# DUCO_Miner_16-01.net
KiCad netlist of a schematic drawn in EAGLE
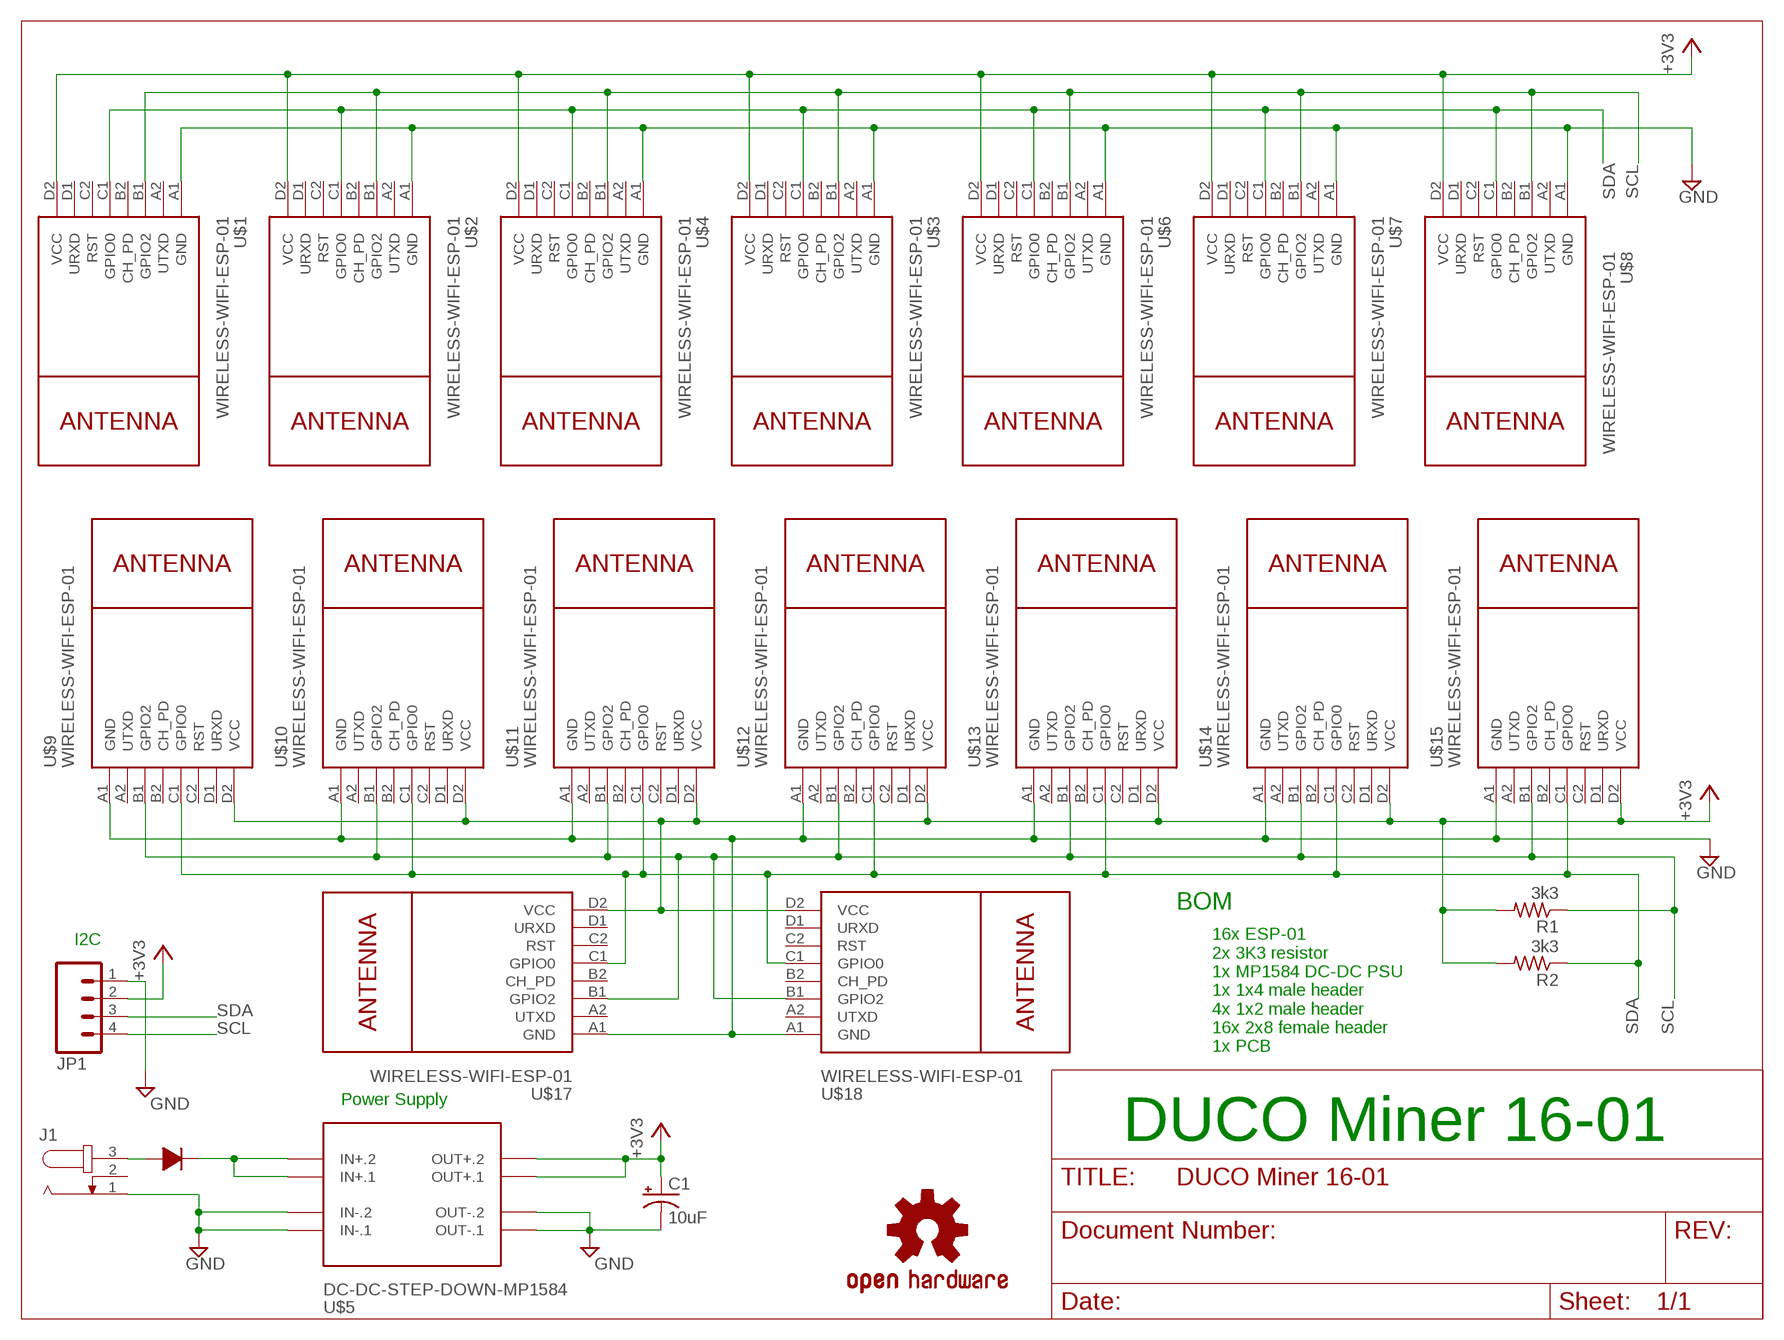
[diagram p0: schematic, sheet 1]

(export (version "E")
  (design (tool "Eeschema 10.0.6"))
  (components
    (comp (ref "C1")
      (value "10uF")
      (footprint "eagle-import:E2-5")
      (libsource (lib "eagle-import") (part "CPOL-USE2-5"))
    )
    (comp (ref "J1")
      (value "JACK-PLUG0")
      (footprint "eagle-import:SPC4077")
      (libsource (lib "eagle-import") (part "JACK-PLUG0"))
    )
    (comp (ref "JP1")
      (value "M04PTH")
      (footprint "eagle-import:1X04")
      (libsource (lib "eagle-import") (part "M04PTH"))
    )
    (comp (ref "LOGO1")
      (value "OSHW-LOGOL")
      (footprint "eagle-import:OSHW-LOGO-L")
      (libsource (lib "eagle-import") (part "OSHW-LOGOL"))
    )
    (comp (ref "R1")
      (value "3k3")
      (footprint "eagle-import:0204_7")
      (libsource (lib "eagle-import") (part "R-US_0204/7"))
    )
    (comp (ref "R2")
      (value "3k3")
      (footprint "eagle-import:0204_7")
      (libsource (lib "eagle-import") (part "R-US_0204/7"))
    )
    (comp (ref "U$1")
      (value "WIRELESS-WIFI-ESP-01")
      (footprint "eagle-import:WIRELESS-WIFI-ESP-01")
      (libsource (lib "eagle-import") (part "WIRELESS-WIFI-ESP-01"))
    )
    (comp (ref "U$2")
      (value "WIRELESS-WIFI-ESP-01")
      (footprint "eagle-import:WIRELESS-WIFI-ESP-01")
      (libsource (lib "eagle-import") (part "WIRELESS-WIFI-ESP-01"))
    )
    (comp (ref "U$3")
      (value "WIRELESS-WIFI-ESP-01")
      (footprint "eagle-import:WIRELESS-WIFI-ESP-01")
      (libsource (lib "eagle-import") (part "WIRELESS-WIFI-ESP-01"))
    )
    (comp (ref "U$4")
      (value "WIRELESS-WIFI-ESP-01")
      (footprint "eagle-import:WIRELESS-WIFI-ESP-01")
      (libsource (lib "eagle-import") (part "WIRELESS-WIFI-ESP-01"))
    )
    (comp (ref "U$5")
      (value "DC-DC-STEP-DOWN-MP1584")
      (footprint "eagle-import:DC-DC-STEP-DOWN-MP1584")
      (libsource (lib "eagle-import") (part "DC-DC-STEP-DOWN-MP1584"))
    )
    (comp (ref "U$6")
      (value "WIRELESS-WIFI-ESP-01")
      (footprint "eagle-import:WIRELESS-WIFI-ESP-01")
      (libsource (lib "eagle-import") (part "WIRELESS-WIFI-ESP-01"))
    )
    (comp (ref "U$7")
      (value "WIRELESS-WIFI-ESP-01")
      (footprint "eagle-import:WIRELESS-WIFI-ESP-01")
      (libsource (lib "eagle-import") (part "WIRELESS-WIFI-ESP-01"))
    )
    (comp (ref "U$8")
      (value "WIRELESS-WIFI-ESP-01")
      (footprint "eagle-import:WIRELESS-WIFI-ESP-01")
      (libsource (lib "eagle-import") (part "WIRELESS-WIFI-ESP-01"))
    )
    (comp (ref "U$9")
      (value "WIRELESS-WIFI-ESP-01")
      (footprint "eagle-import:WIRELESS-WIFI-ESP-01")
      (libsource (lib "eagle-import") (part "WIRELESS-WIFI-ESP-01"))
    )
    (comp (ref "U$10")
      (value "WIRELESS-WIFI-ESP-01")
      (footprint "eagle-import:WIRELESS-WIFI-ESP-01")
      (libsource (lib "eagle-import") (part "WIRELESS-WIFI-ESP-01"))
    )
    (comp (ref "U$11")
      (value "WIRELESS-WIFI-ESP-01")
      (footprint "eagle-import:WIRELESS-WIFI-ESP-01")
      (libsource (lib "eagle-import") (part "WIRELESS-WIFI-ESP-01"))
    )
    (comp (ref "U$12")
      (value "WIRELESS-WIFI-ESP-01")
      (footprint "eagle-import:WIRELESS-WIFI-ESP-01")
      (libsource (lib "eagle-import") (part "WIRELESS-WIFI-ESP-01"))
    )
    (comp (ref "U$13")
      (value "WIRELESS-WIFI-ESP-01")
      (footprint "eagle-import:WIRELESS-WIFI-ESP-01")
      (libsource (lib "eagle-import") (part "WIRELESS-WIFI-ESP-01"))
    )
    (comp (ref "U$14")
      (value "WIRELESS-WIFI-ESP-01")
      (footprint "eagle-import:WIRELESS-WIFI-ESP-01")
      (libsource (lib "eagle-import") (part "WIRELESS-WIFI-ESP-01"))
    )
    (comp (ref "U$15")
      (value "WIRELESS-WIFI-ESP-01")
      (footprint "eagle-import:WIRELESS-WIFI-ESP-01")
      (libsource (lib "eagle-import") (part "WIRELESS-WIFI-ESP-01"))
    )
    (comp (ref "U$16")
      (value "1N4001")
      (footprint "eagle-import:DIODE-12.70")
      (libsource (lib "eagle-import") (part "1N4001"))
    )
    (comp (ref "U$17")
      (value "WIRELESS-WIFI-ESP-01")
      (footprint "eagle-import:WIRELESS-WIFI-ESP-01")
      (libsource (lib "eagle-import") (part "WIRELESS-WIFI-ESP-01"))
    )
    (comp (ref "U$18")
      (value "WIRELESS-WIFI-ESP-01")
      (footprint "eagle-import:WIRELESS-WIFI-ESP-01")
      (libsource (lib "eagle-import") (part "WIRELESS-WIFI-ESP-01"))
    )
  )
  (nets
    (net (code "1") (name "+3V3") (class "Default")
      (node (ref "C1") (pin "+") (pinfunction "+_+") (pintype "passive"))
      (node (ref "JP1") (pin "2") (pinfunction "2_2") (pintype "passive"))
      (node (ref "R1") (pin "2") (pinfunction "2_2") (pintype "passive"))
      (node (ref "R2") (pin "2") (pinfunction "2_2") (pintype "passive"))
      (node (ref "U$1") (pin "D2") (pinfunction "VCC_D2") (pintype "power_in"))
      (node (ref "U$10") (pin "D2") (pinfunction "VCC_D2") (pintype "power_in"))
      (node (ref "U$11") (pin "D2") (pinfunction "VCC_D2") (pintype "power_in"))
      (node (ref "U$12") (pin "D2") (pinfunction "VCC_D2") (pintype "power_in"))
      (node (ref "U$13") (pin "D2") (pinfunction "VCC_D2") (pintype "power_in"))
      (node (ref "U$14") (pin "D2") (pinfunction "VCC_D2") (pintype "power_in"))
      (node (ref "U$15") (pin "D2") (pinfunction "VCC_D2") (pintype "power_in"))
      (node (ref "U$17") (pin "D2") (pinfunction "VCC_D2") (pintype "power_in"))
      (node (ref "U$18") (pin "D2") (pinfunction "VCC_D2") (pintype "power_in"))
      (node (ref "U$2") (pin "D2") (pinfunction "VCC_D2") (pintype "power_in"))
      (node (ref "U$3") (pin "D2") (pinfunction "VCC_D2") (pintype "power_in"))
      (node (ref "U$4") (pin "D2") (pinfunction "VCC_D2") (pintype "power_in"))
      (node (ref "U$5") (pin "OUT+.1") (pinfunction "OUT+.1_OUT+.1") (pintype "bidirectional"))
      (node (ref "U$5") (pin "OUT+.2") (pinfunction "OUT+.2_OUT+.2") (pintype "bidirectional"))
      (node (ref "U$6") (pin "D2") (pinfunction "VCC_D2") (pintype "power_in"))
      (node (ref "U$7") (pin "D2") (pinfunction "VCC_D2") (pintype "power_in"))
      (node (ref "U$8") (pin "D2") (pinfunction "VCC_D2") (pintype "power_in"))
      (node (ref "U$9") (pin "D2") (pinfunction "VCC_D2") (pintype "power_in"))
    )
    (net (code "2") (name "/SCL") (class "Default")
      (node (ref "JP1") (pin "4") (pinfunction "4_4") (pintype "passive"))
      (node (ref "R1") (pin "1") (pinfunction "1_1") (pintype "passive"))
      (node (ref "U$1") (pin "B1") (pinfunction "GPIO2_B1") (pintype "bidirectional"))
      (node (ref "U$10") (pin "B1") (pinfunction "GPIO2_B1") (pintype "bidirectional"))
      (node (ref "U$11") (pin "B1") (pinfunction "GPIO2_B1") (pintype "bidirectional"))
      (node (ref "U$12") (pin "B1") (pinfunction "GPIO2_B1") (pintype "bidirectional"))
      (node (ref "U$13") (pin "B1") (pinfunction "GPIO2_B1") (pintype "bidirectional"))
      (node (ref "U$14") (pin "B1") (pinfunction "GPIO2_B1") (pintype "bidirectional"))
      (node (ref "U$15") (pin "B1") (pinfunction "GPIO2_B1") (pintype "bidirectional"))
      (node (ref "U$17") (pin "B1") (pinfunction "GPIO2_B1") (pintype "bidirectional"))
      (node (ref "U$18") (pin "B1") (pinfunction "GPIO2_B1") (pintype "bidirectional"))
      (node (ref "U$2") (pin "B1") (pinfunction "GPIO2_B1") (pintype "bidirectional"))
      (node (ref "U$3") (pin "B1") (pinfunction "GPIO2_B1") (pintype "bidirectional"))
      (node (ref "U$4") (pin "B1") (pinfunction "GPIO2_B1") (pintype "bidirectional"))
      (node (ref "U$6") (pin "B1") (pinfunction "GPIO2_B1") (pintype "bidirectional"))
      (node (ref "U$7") (pin "B1") (pinfunction "GPIO2_B1") (pintype "bidirectional"))
      (node (ref "U$8") (pin "B1") (pinfunction "GPIO2_B1") (pintype "bidirectional"))
      (node (ref "U$9") (pin "B1") (pinfunction "GPIO2_B1") (pintype "bidirectional"))
    )
    (net (code "3") (name "/SDA") (class "Default")
      (node (ref "JP1") (pin "3") (pinfunction "3_3") (pintype "passive"))
      (node (ref "R2") (pin "1") (pinfunction "1_1") (pintype "passive"))
      (node (ref "U$1") (pin "C1") (pinfunction "GPIO0_C1") (pintype "bidirectional"))
      (node (ref "U$10") (pin "C1") (pinfunction "GPIO0_C1") (pintype "bidirectional"))
      (node (ref "U$11") (pin "C1") (pinfunction "GPIO0_C1") (pintype "bidirectional"))
      (node (ref "U$12") (pin "C1") (pinfunction "GPIO0_C1") (pintype "bidirectional"))
      (node (ref "U$13") (pin "C1") (pinfunction "GPIO0_C1") (pintype "bidirectional"))
      (node (ref "U$14") (pin "C1") (pinfunction "GPIO0_C1") (pintype "bidirectional"))
      (node (ref "U$15") (pin "C1") (pinfunction "GPIO0_C1") (pintype "bidirectional"))
      (node (ref "U$17") (pin "C1") (pinfunction "GPIO0_C1") (pintype "bidirectional"))
      (node (ref "U$18") (pin "C1") (pinfunction "GPIO0_C1") (pintype "bidirectional"))
      (node (ref "U$2") (pin "C1") (pinfunction "GPIO0_C1") (pintype "bidirectional"))
      (node (ref "U$3") (pin "C1") (pinfunction "GPIO0_C1") (pintype "bidirectional"))
      (node (ref "U$4") (pin "C1") (pinfunction "GPIO0_C1") (pintype "bidirectional"))
      (node (ref "U$6") (pin "C1") (pinfunction "GPIO0_C1") (pintype "bidirectional"))
      (node (ref "U$7") (pin "C1") (pinfunction "GPIO0_C1") (pintype "bidirectional"))
      (node (ref "U$8") (pin "C1") (pinfunction "GPIO0_C1") (pintype "bidirectional"))
      (node (ref "U$9") (pin "C1") (pinfunction "GPIO0_C1") (pintype "bidirectional"))
    )
    (net (code "4") (name "GND") (class "Default")
      (node (ref "C1") (pin "-") (pinfunction "-_-") (pintype "passive"))
      (node (ref "J1") (pin "1") (pinfunction "1_1") (pintype "passive"))
      (node (ref "JP1") (pin "1") (pinfunction "1_1") (pintype "passive"))
      (node (ref "U$1") (pin "A1") (pinfunction "GND_A1") (pintype "power_in"))
      (node (ref "U$10") (pin "A1") (pinfunction "GND_A1") (pintype "power_in"))
      (node (ref "U$11") (pin "A1") (pinfunction "GND_A1") (pintype "power_in"))
      (node (ref "U$12") (pin "A1") (pinfunction "GND_A1") (pintype "power_in"))
      (node (ref "U$13") (pin "A1") (pinfunction "GND_A1") (pintype "power_in"))
      (node (ref "U$14") (pin "A1") (pinfunction "GND_A1") (pintype "power_in"))
      (node (ref "U$15") (pin "A1") (pinfunction "GND_A1") (pintype "power_in"))
      (node (ref "U$17") (pin "A1") (pinfunction "GND_A1") (pintype "power_in"))
      (node (ref "U$18") (pin "A1") (pinfunction "GND_A1") (pintype "power_in"))
      (node (ref "U$2") (pin "A1") (pinfunction "GND_A1") (pintype "power_in"))
      (node (ref "U$3") (pin "A1") (pinfunction "GND_A1") (pintype "power_in"))
      (node (ref "U$4") (pin "A1") (pinfunction "GND_A1") (pintype "power_in"))
      (node (ref "U$5") (pin "IN-.1") (pinfunction "IN-.1_IN-.1") (pintype "bidirectional"))
      (node (ref "U$5") (pin "IN-.2") (pinfunction "IN-.2_IN-.2") (pintype "bidirectional"))
      (node (ref "U$5") (pin "OUT-.1") (pinfunction "OUT-.1_OUT-.1") (pintype "bidirectional"))
      (node (ref "U$5") (pin "OUT-.2") (pinfunction "OUT-.2_OUT-.2") (pintype "bidirectional"))
      (node (ref "U$6") (pin "A1") (pinfunction "GND_A1") (pintype "power_in"))
      (node (ref "U$7") (pin "A1") (pinfunction "GND_A1") (pintype "power_in"))
      (node (ref "U$8") (pin "A1") (pinfunction "GND_A1") (pintype "power_in"))
      (node (ref "U$9") (pin "A1") (pinfunction "GND_A1") (pintype "power_in"))
    )
    (net (code "5") (name "Net-(J1-Pad3)") (class "Default")
      (node (ref "J1") (pin "3") (pinfunction "3_3") (pintype "passive"))
      (node (ref "U$16") (pin "P$1") (pinfunction "P$1_P$1") (pintype "passive"))
    )
    (net (code "6") (name "Net-(U$16-PadP$2)") (class "Default")
      (node (ref "U$16") (pin "P$2") (pinfunction "P$2_P$2") (pintype "passive"))
      (node (ref "U$5") (pin "IN+.1") (pinfunction "IN+.1_IN+.1") (pintype "bidirectional"))
      (node (ref "U$5") (pin "IN+.2") (pinfunction "IN+.2_IN+.2") (pintype "bidirectional"))
    )
    (net (code "7") (name "unconnected-(J1-Pad2)") (class "Default")
      (node (ref "J1") (pin "2") (pinfunction "2_2") (pintype "passive"))
    )
    (net (code "8") (name "unconnected-(U$1-CH_PD-PadB2)") (class "Default")
      (node (ref "U$1") (pin "B2") (pinfunction "CH_PD_B2") (pintype "bidirectional"))
    )
    (net (code "9") (name "unconnected-(U$1-RST-PadC2)") (class "Default")
      (node (ref "U$1") (pin "C2") (pinfunction "RST_C2") (pintype "bidirectional"))
    )
    (net (code "10") (name "unconnected-(U$1-URXD-PadD1)") (class "Default")
      (node (ref "U$1") (pin "D1") (pinfunction "URXD_D1") (pintype "bidirectional"))
    )
    (net (code "11") (name "unconnected-(U$1-UTXD-PadA2)") (class "Default")
      (node (ref "U$1") (pin "A2") (pinfunction "UTXD_A2") (pintype "bidirectional"))
    )
    (net (code "12") (name "unconnected-(U$2-CH_PD-PadB2)") (class "Default")
      (node (ref "U$2") (pin "B2") (pinfunction "CH_PD_B2") (pintype "bidirectional"))
    )
    (net (code "13") (name "unconnected-(U$2-RST-PadC2)") (class "Default")
      (node (ref "U$2") (pin "C2") (pinfunction "RST_C2") (pintype "bidirectional"))
    )
    (net (code "14") (name "unconnected-(U$2-URXD-PadD1)") (class "Default")
      (node (ref "U$2") (pin "D1") (pinfunction "URXD_D1") (pintype "bidirectional"))
    )
    (net (code "15") (name "unconnected-(U$2-UTXD-PadA2)") (class "Default")
      (node (ref "U$2") (pin "A2") (pinfunction "UTXD_A2") (pintype "bidirectional"))
    )
    (net (code "16") (name "unconnected-(U$3-CH_PD-PadB2)") (class "Default")
      (node (ref "U$3") (pin "B2") (pinfunction "CH_PD_B2") (pintype "bidirectional"))
    )
    (net (code "17") (name "unconnected-(U$3-RST-PadC2)") (class "Default")
      (node (ref "U$3") (pin "C2") (pinfunction "RST_C2") (pintype "bidirectional"))
    )
    (net (code "18") (name "unconnected-(U$3-URXD-PadD1)") (class "Default")
      (node (ref "U$3") (pin "D1") (pinfunction "URXD_D1") (pintype "bidirectional"))
    )
    (net (code "19") (name "unconnected-(U$3-UTXD-PadA2)") (class "Default")
      (node (ref "U$3") (pin "A2") (pinfunction "UTXD_A2") (pintype "bidirectional"))
    )
    (net (code "20") (name "unconnected-(U$4-CH_PD-PadB2)") (class "Default")
      (node (ref "U$4") (pin "B2") (pinfunction "CH_PD_B2") (pintype "bidirectional"))
    )
    (net (code "21") (name "unconnected-(U$4-RST-PadC2)") (class "Default")
      (node (ref "U$4") (pin "C2") (pinfunction "RST_C2") (pintype "bidirectional"))
    )
    (net (code "22") (name "unconnected-(U$4-URXD-PadD1)") (class "Default")
      (node (ref "U$4") (pin "D1") (pinfunction "URXD_D1") (pintype "bidirectional"))
    )
    (net (code "23") (name "unconnected-(U$4-UTXD-PadA2)") (class "Default")
      (node (ref "U$4") (pin "A2") (pinfunction "UTXD_A2") (pintype "bidirectional"))
    )
    (net (code "24") (name "unconnected-(U$6-CH_PD-PadB2)") (class "Default")
      (node (ref "U$6") (pin "B2") (pinfunction "CH_PD_B2") (pintype "bidirectional"))
    )
    (net (code "25") (name "unconnected-(U$6-RST-PadC2)") (class "Default")
      (node (ref "U$6") (pin "C2") (pinfunction "RST_C2") (pintype "bidirectional"))
    )
    (net (code "26") (name "unconnected-(U$6-URXD-PadD1)") (class "Default")
      (node (ref "U$6") (pin "D1") (pinfunction "URXD_D1") (pintype "bidirectional"))
    )
    (net (code "27") (name "unconnected-(U$6-UTXD-PadA2)") (class "Default")
      (node (ref "U$6") (pin "A2") (pinfunction "UTXD_A2") (pintype "bidirectional"))
    )
    (net (code "28") (name "unconnected-(U$7-CH_PD-PadB2)") (class "Default")
      (node (ref "U$7") (pin "B2") (pinfunction "CH_PD_B2") (pintype "bidirectional"))
    )
    (net (code "29") (name "unconnected-(U$7-RST-PadC2)") (class "Default")
      (node (ref "U$7") (pin "C2") (pinfunction "RST_C2") (pintype "bidirectional"))
    )
    (net (code "30") (name "unconnected-(U$7-URXD-PadD1)") (class "Default")
      (node (ref "U$7") (pin "D1") (pinfunction "URXD_D1") (pintype "bidirectional"))
    )
    (net (code "31") (name "unconnected-(U$7-UTXD-PadA2)") (class "Default")
      (node (ref "U$7") (pin "A2") (pinfunction "UTXD_A2") (pintype "bidirectional"))
    )
    (net (code "32") (name "unconnected-(U$8-CH_PD-PadB2)") (class "Default")
      (node (ref "U$8") (pin "B2") (pinfunction "CH_PD_B2") (pintype "bidirectional"))
    )
    (net (code "33") (name "unconnected-(U$8-RST-PadC2)") (class "Default")
      (node (ref "U$8") (pin "C2") (pinfunction "RST_C2") (pintype "bidirectional"))
    )
    (net (code "34") (name "unconnected-(U$8-URXD-PadD1)") (class "Default")
      (node (ref "U$8") (pin "D1") (pinfunction "URXD_D1") (pintype "bidirectional"))
    )
    (net (code "35") (name "unconnected-(U$8-UTXD-PadA2)") (class "Default")
      (node (ref "U$8") (pin "A2") (pinfunction "UTXD_A2") (pintype "bidirectional"))
    )
    (net (code "36") (name "unconnected-(U$9-CH_PD-PadB2)") (class "Default")
      (node (ref "U$9") (pin "B2") (pinfunction "CH_PD_B2") (pintype "bidirectional"))
    )
    (net (code "37") (name "unconnected-(U$9-RST-PadC2)") (class "Default")
      (node (ref "U$9") (pin "C2") (pinfunction "RST_C2") (pintype "bidirectional"))
    )
    (net (code "38") (name "unconnected-(U$9-URXD-PadD1)") (class "Default")
      (node (ref "U$9") (pin "D1") (pinfunction "URXD_D1") (pintype "bidirectional"))
    )
    (net (code "39") (name "unconnected-(U$9-UTXD-PadA2)") (class "Default")
      (node (ref "U$9") (pin "A2") (pinfunction "UTXD_A2") (pintype "bidirectional"))
    )
    (net (code "40") (name "unconnected-(U$10-CH_PD-PadB2)") (class "Default")
      (node (ref "U$10") (pin "B2") (pinfunction "CH_PD_B2") (pintype "bidirectional"))
    )
    (net (code "41") (name "unconnected-(U$10-RST-PadC2)") (class "Default")
      (node (ref "U$10") (pin "C2") (pinfunction "RST_C2") (pintype "bidirectional"))
    )
    (net (code "42") (name "unconnected-(U$10-URXD-PadD1)") (class "Default")
      (node (ref "U$10") (pin "D1") (pinfunction "URXD_D1") (pintype "bidirectional"))
    )
    (net (code "43") (name "unconnected-(U$10-UTXD-PadA2)") (class "Default")
      (node (ref "U$10") (pin "A2") (pinfunction "UTXD_A2") (pintype "bidirectional"))
    )
    (net (code "44") (name "unconnected-(U$11-CH_PD-PadB2)") (class "Default")
      (node (ref "U$11") (pin "B2") (pinfunction "CH_PD_B2") (pintype "bidirectional"))
    )
    (net (code "45") (name "unconnected-(U$11-RST-PadC2)") (class "Default")
      (node (ref "U$11") (pin "C2") (pinfunction "RST_C2") (pintype "bidirectional"))
    )
    (net (code "46") (name "unconnected-(U$11-URXD-PadD1)") (class "Default")
      (node (ref "U$11") (pin "D1") (pinfunction "URXD_D1") (pintype "bidirectional"))
    )
    (net (code "47") (name "unconnected-(U$11-UTXD-PadA2)") (class "Default")
      (node (ref "U$11") (pin "A2") (pinfunction "UTXD_A2") (pintype "bidirectional"))
    )
    (net (code "48") (name "unconnected-(U$12-CH_PD-PadB2)") (class "Default")
      (node (ref "U$12") (pin "B2") (pinfunction "CH_PD_B2") (pintype "bidirectional"))
    )
    (net (code "49") (name "unconnected-(U$12-RST-PadC2)") (class "Default")
      (node (ref "U$12") (pin "C2") (pinfunction "RST_C2") (pintype "bidirectional"))
    )
    (net (code "50") (name "unconnected-(U$12-URXD-PadD1)") (class "Default")
      (node (ref "U$12") (pin "D1") (pinfunction "URXD_D1") (pintype "bidirectional"))
    )
    (net (code "51") (name "unconnected-(U$12-UTXD-PadA2)") (class "Default")
      (node (ref "U$12") (pin "A2") (pinfunction "UTXD_A2") (pintype "bidirectional"))
    )
    (net (code "52") (name "unconnected-(U$13-CH_PD-PadB2)") (class "Default")
      (node (ref "U$13") (pin "B2") (pinfunction "CH_PD_B2") (pintype "bidirectional"))
    )
    (net (code "53") (name "unconnected-(U$13-RST-PadC2)") (class "Default")
      (node (ref "U$13") (pin "C2") (pinfunction "RST_C2") (pintype "bidirectional"))
    )
    (net (code "54") (name "unconnected-(U$13-URXD-PadD1)") (class "Default")
      (node (ref "U$13") (pin "D1") (pinfunction "URXD_D1") (pintype "bidirectional"))
    )
    (net (code "55") (name "unconnected-(U$13-UTXD-PadA2)") (class "Default")
      (node (ref "U$13") (pin "A2") (pinfunction "UTXD_A2") (pintype "bidirectional"))
    )
    (net (code "56") (name "unconnected-(U$14-CH_PD-PadB2)") (class "Default")
      (node (ref "U$14") (pin "B2") (pinfunction "CH_PD_B2") (pintype "bidirectional"))
    )
    (net (code "57") (name "unconnected-(U$14-RST-PadC2)") (class "Default")
      (node (ref "U$14") (pin "C2") (pinfunction "RST_C2") (pintype "bidirectional"))
    )
    (net (code "58") (name "unconnected-(U$14-URXD-PadD1)") (class "Default")
      (node (ref "U$14") (pin "D1") (pinfunction "URXD_D1") (pintype "bidirectional"))
    )
    (net (code "59") (name "unconnected-(U$14-UTXD-PadA2)") (class "Default")
      (node (ref "U$14") (pin "A2") (pinfunction "UTXD_A2") (pintype "bidirectional"))
    )
    (net (code "60") (name "unconnected-(U$15-CH_PD-PadB2)") (class "Default")
      (node (ref "U$15") (pin "B2") (pinfunction "CH_PD_B2") (pintype "bidirectional"))
    )
    (net (code "61") (name "unconnected-(U$15-RST-PadC2)") (class "Default")
      (node (ref "U$15") (pin "C2") (pinfunction "RST_C2") (pintype "bidirectional"))
    )
    (net (code "62") (name "unconnected-(U$15-URXD-PadD1)") (class "Default")
      (node (ref "U$15") (pin "D1") (pinfunction "URXD_D1") (pintype "bidirectional"))
    )
    (net (code "63") (name "unconnected-(U$15-UTXD-PadA2)") (class "Default")
      (node (ref "U$15") (pin "A2") (pinfunction "UTXD_A2") (pintype "bidirectional"))
    )
    (net (code "64") (name "unconnected-(U$17-CH_PD-PadB2)") (class "Default")
      (node (ref "U$17") (pin "B2") (pinfunction "CH_PD_B2") (pintype "bidirectional"))
    )
    (net (code "65") (name "unconnected-(U$17-RST-PadC2)") (class "Default")
      (node (ref "U$17") (pin "C2") (pinfunction "RST_C2") (pintype "bidirectional"))
    )
    (net (code "66") (name "unconnected-(U$17-URXD-PadD1)") (class "Default")
      (node (ref "U$17") (pin "D1") (pinfunction "URXD_D1") (pintype "bidirectional"))
    )
    (net (code "67") (name "unconnected-(U$17-UTXD-PadA2)") (class "Default")
      (node (ref "U$17") (pin "A2") (pinfunction "UTXD_A2") (pintype "bidirectional"))
    )
    (net (code "68") (name "unconnected-(U$18-CH_PD-PadB2)") (class "Default")
      (node (ref "U$18") (pin "B2") (pinfunction "CH_PD_B2") (pintype "bidirectional"))
    )
    (net (code "69") (name "unconnected-(U$18-RST-PadC2)") (class "Default")
      (node (ref "U$18") (pin "C2") (pinfunction "RST_C2") (pintype "bidirectional"))
    )
    (net (code "70") (name "unconnected-(U$18-URXD-PadD1)") (class "Default")
      (node (ref "U$18") (pin "D1") (pinfunction "URXD_D1") (pintype "bidirectional"))
    )
    (net (code "71") (name "unconnected-(U$18-UTXD-PadA2)") (class "Default")
      (node (ref "U$18") (pin "A2") (pinfunction "UTXD_A2") (pintype "bidirectional"))
    )
  )
)
